# B3F1000.net
KiCad netlist of a schematic drawn in Altium Designer
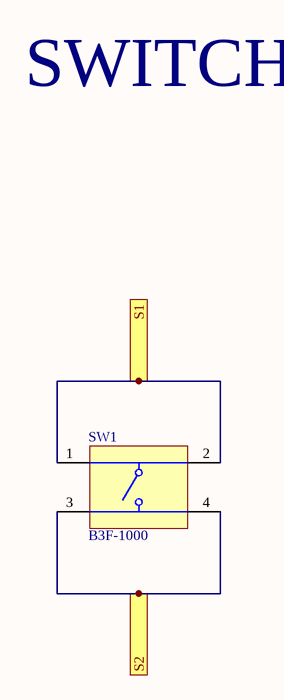
[diagram p0: B3F1000.SchDoc]

(export (version "E")
  (design (tool "Eeschema 10.0.6"))
  (components
    (comp (ref "SW1")
      (value "B3F-1000")
      (footprint "OMRON-B3F-1000-4_V")
      (description "Tactile Switch, SPST-NO, 0.05 A, 5 to 24 V, -25 to 70 degC, 4-Pin THD, RoHS, Bulk")
      (libsource (lib "Altium Content Vault") (part "SW-SPST-4_A"))
    )
  )
  (nets
    (net (code "1") (name "/S1") (class "Default")
      (node (ref "SW1") (pin "1") (pinfunction "1_1") (pintype "passive"))
      (node (ref "SW1") (pin "2") (pinfunction "2_2") (pintype "passive"))
    )
    (net (code "2") (name "/S2") (class "Default")
      (node (ref "SW1") (pin "3") (pinfunction "3_3") (pintype "passive"))
      (node (ref "SW1") (pin "4") (pinfunction "4_4") (pintype "passive"))
    )
  )
)
